# FBridge.net
KiCad netlist of a schematic drawn in Altium Designer
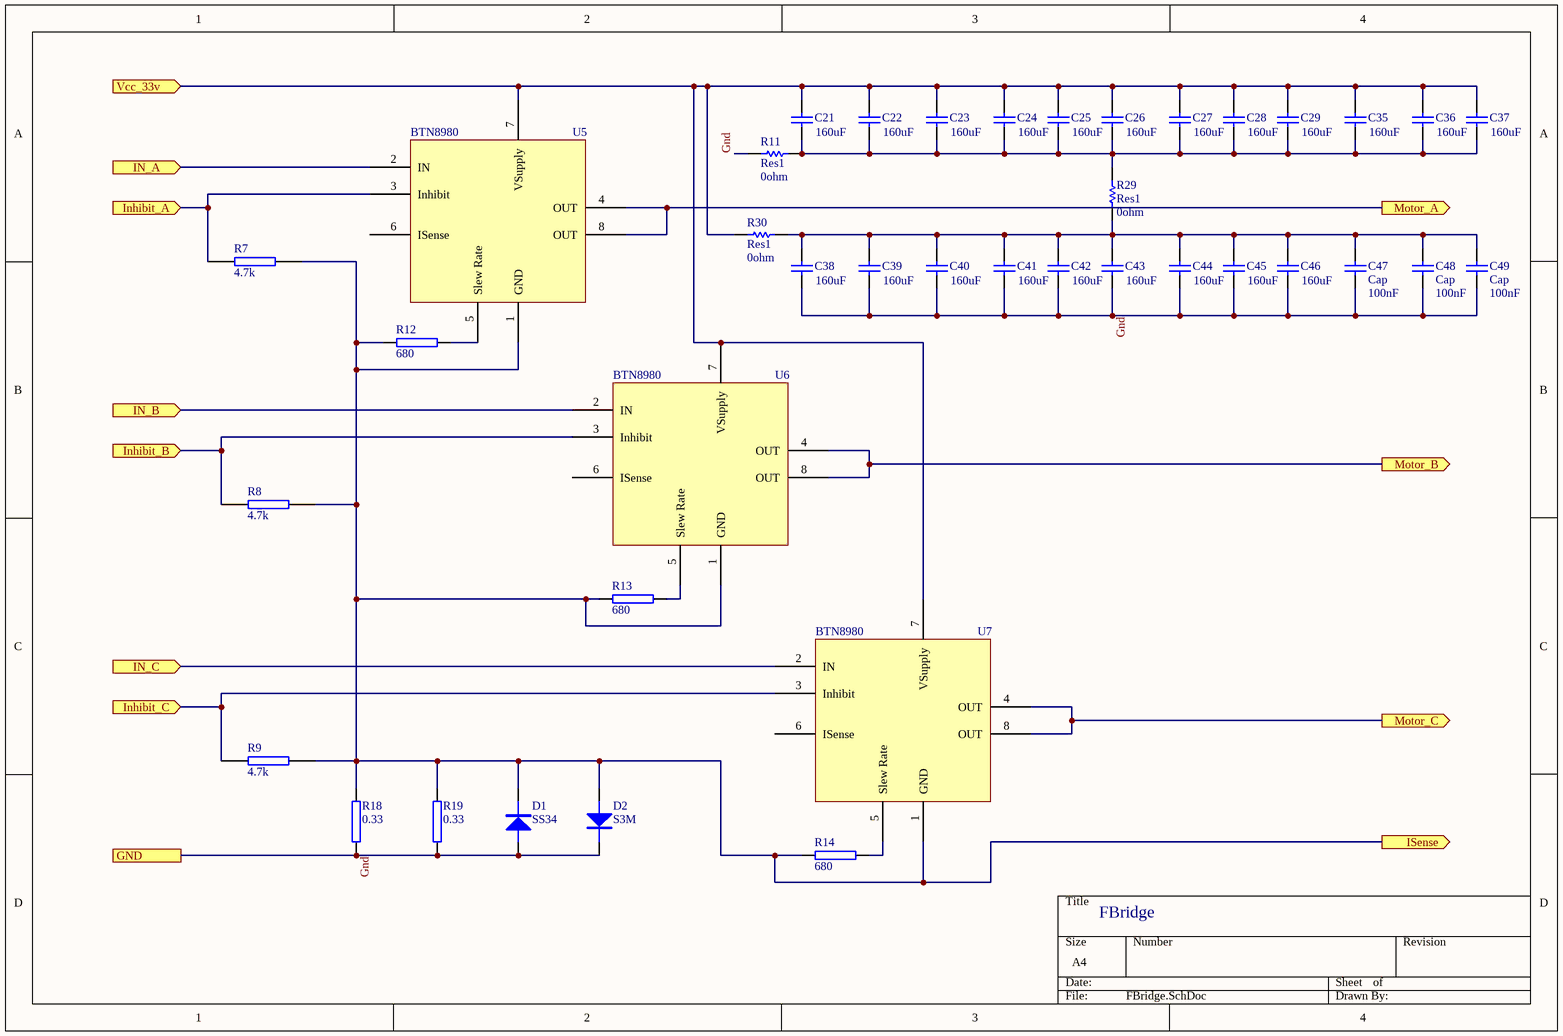
[diagram p0: FBridge.SchDoc]

(export (version "E")
  (design (tool "Eeschema 10.0.6"))
  (components
    (comp (ref "C21")
      (value "160uF")
      (footprint "Tantalum_9545")
      (description "Capacitor")
      (fields (field (name "Comment") "Cap") (field (name "PUBLISHER") "Altium Limited"))
      (libsource (lib "Miscellaneous Devices") (part "Cap"))
    )
    (comp (ref "C22")
      (value "160uF")
      (footprint "Tantalum_9545")
      (description "Capacitor")
      (fields (field (name "Comment") "Cap") (field (name "PUBLISHER") "Altium Limited"))
      (libsource (lib "Miscellaneous Devices") (part "Cap"))
    )
    (comp (ref "C23")
      (value "160uF")
      (footprint "Tantalum_9545")
      (description "Capacitor")
      (fields (field (name "Comment") "Cap") (field (name "PUBLISHER") "Altium Limited"))
      (libsource (lib "Miscellaneous Devices") (part "Cap"))
    )
    (comp (ref "C24")
      (value "160uF")
      (footprint "Tantalum_9545")
      (description "Capacitor")
      (fields (field (name "Comment") "Cap") (field (name "PUBLISHER") "Altium Limited"))
      (libsource (lib "Miscellaneous Devices") (part "Cap"))
    )
    (comp (ref "C25")
      (value "160uF")
      (footprint "Tantalum_9545")
      (description "Capacitor")
      (fields (field (name "Comment") "Cap") (field (name "PUBLISHER") "Altium Limited"))
      (libsource (lib "Miscellaneous Devices") (part "Cap"))
    )
    (comp (ref "C26")
      (value "160uF")
      (footprint "Tantalum_9545")
      (description "Capacitor")
      (fields (field (name "Comment") "Cap") (field (name "PUBLISHER") "Altium Limited"))
      (libsource (lib "Miscellaneous Devices") (part "Cap"))
    )
    (comp (ref "C27")
      (value "160uF")
      (footprint "Tantalum_9545")
      (description "Capacitor")
      (fields (field (name "Comment") "Cap") (field (name "PUBLISHER") "Altium Limited"))
      (libsource (lib "Miscellaneous Devices") (part "Cap"))
    )
    (comp (ref "C28")
      (value "160uF")
      (footprint "Tantalum_9545")
      (description "Capacitor")
      (fields (field (name "Comment") "Cap") (field (name "PUBLISHER") "Altium Limited"))
      (libsource (lib "Miscellaneous Devices") (part "Cap"))
    )
    (comp (ref "C29")
      (value "160uF")
      (footprint "Tantalum_9545")
      (description "Capacitor")
      (fields (field (name "Comment") "Cap") (field (name "PUBLISHER") "Altium Limited"))
      (libsource (lib "Miscellaneous Devices") (part "Cap"))
    )
    (comp (ref "C35")
      (value "160uF")
      (footprint "Tantalum_9545")
      (description "Capacitor")
      (fields (field (name "Comment") "Cap") (field (name "PUBLISHER") "Altium Limited"))
      (libsource (lib "Miscellaneous Devices") (part "Cap"))
    )
    (comp (ref "C36")
      (value "160uF")
      (footprint "Tantalum_9545")
      (description "Capacitor")
      (fields (field (name "Comment") "Cap") (field (name "PUBLISHER") "Altium Limited"))
      (libsource (lib "Miscellaneous Devices") (part "Cap"))
    )
    (comp (ref "C37")
      (value "160uF")
      (footprint "Tantalum_9545")
      (description "Capacitor")
      (fields (field (name "Comment") "Cap") (field (name "PUBLISHER") "Altium Limited"))
      (libsource (lib "Miscellaneous Devices") (part "Cap"))
    )
    (comp (ref "C38")
      (value "160uF")
      (footprint "Tantalum_9545")
      (description "Capacitor")
      (fields (field (name "Comment") "Cap") (field (name "PUBLISHER") "Altium Limited"))
      (libsource (lib "Miscellaneous Devices") (part "Cap"))
    )
    (comp (ref "C39")
      (value "160uF")
      (footprint "Tantalum_9545")
      (description "Capacitor")
      (fields (field (name "Comment") "Cap") (field (name "PUBLISHER") "Altium Limited"))
      (libsource (lib "Miscellaneous Devices") (part "Cap"))
    )
    (comp (ref "C40")
      (value "160uF")
      (footprint "Tantalum_9545")
      (description "Capacitor")
      (fields (field (name "Comment") "Cap") (field (name "PUBLISHER") "Altium Limited"))
      (libsource (lib "Miscellaneous Devices") (part "Cap"))
    )
    (comp (ref "C41")
      (value "160uF")
      (footprint "Tantalum_9545")
      (description "Capacitor")
      (fields (field (name "Comment") "Cap") (field (name "PUBLISHER") "Altium Limited"))
      (libsource (lib "Miscellaneous Devices") (part "Cap"))
    )
    (comp (ref "C42")
      (value "160uF")
      (footprint "Tantalum_9545")
      (description "Capacitor")
      (fields (field (name "Comment") "Cap") (field (name "PUBLISHER") "Altium Limited"))
      (libsource (lib "Miscellaneous Devices") (part "Cap"))
    )
    (comp (ref "C43")
      (value "160uF")
      (footprint "Tantalum_9545")
      (description "Capacitor")
      (fields (field (name "Comment") "Cap") (field (name "PUBLISHER") "Altium Limited"))
      (libsource (lib "Miscellaneous Devices") (part "Cap"))
    )
    (comp (ref "C44")
      (value "160uF")
      (footprint "Tantalum_9545")
      (description "Capacitor")
      (fields (field (name "Comment") "Cap") (field (name "PUBLISHER") "Altium Limited"))
      (libsource (lib "Miscellaneous Devices") (part "Cap"))
    )
    (comp (ref "C45")
      (value "160uF")
      (footprint "Tantalum_9545")
      (description "Capacitor")
      (fields (field (name "Comment") "Cap") (field (name "PUBLISHER") "Altium Limited"))
      (libsource (lib "Miscellaneous Devices") (part "Cap"))
    )
    (comp (ref "C46")
      (value "160uF")
      (footprint "Tantalum_9545")
      (description "Capacitor")
      (fields (field (name "Comment") "Cap") (field (name "PUBLISHER") "Altium Limited"))
      (libsource (lib "Miscellaneous Devices") (part "Cap"))
    )
    (comp (ref "C47")
      (value "Cap")
      (footprint "1206_SMD")
      (description "Capacitor")
      (fields (field (name "ALTIUM_VALUE") "100nF") (field (name "PUBLISHER") "Altium Limited"))
      (libsource (lib "Miscellaneous Devices") (part "Cap"))
    )
    (comp (ref "C48")
      (value "Cap")
      (footprint "1206_SMD")
      (description "Capacitor")
      (fields (field (name "ALTIUM_VALUE") "100nF") (field (name "PUBLISHER") "Altium Limited"))
      (libsource (lib "Miscellaneous Devices") (part "Cap"))
    )
    (comp (ref "C49")
      (value "Cap")
      (footprint "1206_SMD")
      (description "Capacitor")
      (fields (field (name "ALTIUM_VALUE") "100nF") (field (name "PUBLISHER") "Altium Limited"))
      (libsource (lib "Miscellaneous Devices") (part "Cap"))
    )
    (comp (ref "D1") (value "SS34") (footprint "SMA") (libsource (lib "Sch_Lib_24") (part "DIODE")))
    (comp (ref "D2") (value "S3M") (footprint "SMC") (libsource (lib "Sch_Lib_24") (part "DIODE")))
    (comp (ref "R7") (value "4.7k") (footprint "1206_SMD") (libsource (lib "") (part "RES2_1")))
    (comp (ref "R8") (value "4.7k") (footprint "1206_SMD") (libsource (lib "") (part "RES2_1")))
    (comp (ref "R9") (value "4.7k") (footprint "1206_SMD") (libsource (lib "") (part "RES2_1")))
    (comp (ref "R11")
      (value "Res1")
      (footprint "2010_smd")
      (description "Resistor")
      (fields (field (name "ALTIUM_VALUE") "0ohm") (field (name "PUBLISHER") "Altium Limited"))
      (libsource (lib "Miscellaneous Devices") (part "Res1"))
    )
    (comp (ref "R12") (value "680") (footprint "1206_SMD") (libsource (lib "Sch_Lib_24") (part "RES2")))
    (comp (ref "R13") (value "680") (footprint "1206_SMD") (libsource (lib "Sch_Lib_24") (part "RES2")))
    (comp (ref "R14") (value "680") (footprint "1206_SMD") (libsource (lib "Sch_Lib_24") (part "RES2")))
    (comp (ref "R18") (value "0.33") (footprint "2010_smd") (libsource (lib "Sch_Lib_24") (part "RES2")))
    (comp (ref "R19") (value "0.33") (footprint "2010_smd") (libsource (lib "Sch_Lib_24") (part "RES2")))
    (comp (ref "R29")
      (value "Res1")
      (footprint "2010_smd")
      (description "Resistor")
      (fields (field (name "ALTIUM_VALUE") "0ohm") (field (name "PUBLISHER") "Altium Limited"))
      (libsource (lib "Miscellaneous Devices") (part "Res1"))
    )
    (comp (ref "R30")
      (value "Res1")
      (footprint "2010_smd")
      (description "Resistor")
      (fields (field (name "ALTIUM_VALUE") "0ohm") (field (name "PUBLISHER") "Altium Limited"))
      (libsource (lib "Miscellaneous Devices") (part "Res1"))
    )
    (comp (ref "U5") (value "BTN8980") (footprint "TO263_7") (libsource (lib "Sch_Lib_24") (part "BTN8980")))
    (comp (ref "U6") (value "BTN8980") (footprint "TO263_7") (libsource (lib "Sch_Lib_24") (part "BTN8980")))
    (comp (ref "U7") (value "BTN8980") (footprint "TO263_7") (libsource (lib "Sch_Lib_24") (part "BTN8980")))
  )
  (nets
    (net (code "1") (name "/Gnd") (class "Default")
      (node (ref "C38") (pin "2") (pinfunction "2_2") (pintype "passive"))
      (node (ref "C39") (pin "2") (pinfunction "2_2") (pintype "passive"))
      (node (ref "C40") (pin "2") (pinfunction "2_2") (pintype "passive"))
      (node (ref "C41") (pin "2") (pinfunction "2_2") (pintype "passive"))
      (node (ref "C42") (pin "2") (pinfunction "2_2") (pintype "passive"))
      (node (ref "C43") (pin "2") (pinfunction "2_2") (pintype "passive"))
      (node (ref "C44") (pin "2") (pinfunction "2_2") (pintype "passive"))
      (node (ref "C45") (pin "2") (pinfunction "2_2") (pintype "passive"))
      (node (ref "C46") (pin "2") (pinfunction "2_2") (pintype "passive"))
      (node (ref "C47") (pin "1") (pinfunction "1_1") (pintype "passive"))
      (node (ref "C48") (pin "1") (pinfunction "1_1") (pintype "passive"))
      (node (ref "C49") (pin "1") (pinfunction "1_1") (pintype "passive"))
      (node (ref "D1") (pin "A") (pintype "passive"))
      (node (ref "D2") (pin "K") (pintype "passive"))
      (node (ref "R11") (pin "1") (pinfunction "1_1") (pintype "passive"))
      (node (ref "R18") (pin "1") (pintype "passive"))
      (node (ref "R19") (pin "1") (pintype "passive"))
    )
    (net (code "2") (name "/IN_A") (class "Default")
      (node (ref "U5") (pin "2") (pinfunction "IN_2") (pintype "passive"))
    )
    (net (code "3") (name "/IN_B") (class "Default")
      (node (ref "U6") (pin "2") (pinfunction "IN_2") (pintype "passive"))
    )
    (net (code "4") (name "/IN_C") (class "Default")
      (node (ref "U7") (pin "2") (pinfunction "IN_2") (pintype "passive"))
    )
    (net (code "5") (name "/ISense") (class "Default")
      (node (ref "D1") (pin "K") (pintype "passive"))
      (node (ref "D2") (pin "A") (pintype "passive"))
      (node (ref "R12") (pin "2") (pintype "passive"))
      (node (ref "R13") (pin "2") (pintype "passive"))
      (node (ref "R14") (pin "2") (pintype "passive"))
      (node (ref "R18") (pin "2") (pintype "passive"))
      (node (ref "R19") (pin "2") (pintype "passive"))
      (node (ref "R7") (pin "2") (pinfunction "2_2") (pintype "passive"))
      (node (ref "R8") (pin "2") (pinfunction "2_2") (pintype "passive"))
      (node (ref "R9") (pin "2") (pinfunction "2_2") (pintype "passive"))
      (node (ref "U5") (pin "1") (pinfunction "GND_1") (pintype "passive"))
      (node (ref "U6") (pin "1") (pinfunction "GND_1") (pintype "passive"))
      (node (ref "U7") (pin "1") (pinfunction "GND_1") (pintype "passive"))
    )
    (net (code "6") (name "/Inhibit_A") (class "Default")
      (node (ref "R7") (pin "1") (pinfunction "1_1") (pintype "passive"))
      (node (ref "U5") (pin "3") (pinfunction "Inhibit_3") (pintype "passive"))
    )
    (net (code "7") (name "/Inhibit_B") (class "Default")
      (node (ref "R8") (pin "1") (pinfunction "1_1") (pintype "passive"))
      (node (ref "U6") (pin "3") (pinfunction "Inhibit_3") (pintype "passive"))
    )
    (net (code "8") (name "/Inhibit_C") (class "Default")
      (node (ref "R9") (pin "1") (pinfunction "1_1") (pintype "passive"))
      (node (ref "U7") (pin "3") (pinfunction "Inhibit_3") (pintype "passive"))
    )
    (net (code "9") (name "/Motor_A") (class "Default")
      (node (ref "U5") (pin "4") (pinfunction "OUT_4") (pintype "passive"))
      (node (ref "U5") (pin "8") (pinfunction "OUT_8") (pintype "passive"))
    )
    (net (code "10") (name "/Motor_B") (class "Default")
      (node (ref "U6") (pin "4") (pinfunction "OUT_4") (pintype "passive"))
      (node (ref "U6") (pin "8") (pinfunction "OUT_8") (pintype "passive"))
    )
    (net (code "11") (name "/Motor_C") (class "Default")
      (node (ref "U7") (pin "4") (pinfunction "OUT_4") (pintype "passive"))
      (node (ref "U7") (pin "8") (pinfunction "OUT_8") (pintype "passive"))
    )
    (net (code "12") (name "/Vcc_33v") (class "Default")
      (node (ref "C21") (pin "1") (pinfunction "1_1") (pintype "passive"))
      (node (ref "C22") (pin "1") (pinfunction "1_1") (pintype "passive"))
      (node (ref "C23") (pin "1") (pinfunction "1_1") (pintype "passive"))
      (node (ref "C24") (pin "1") (pinfunction "1_1") (pintype "passive"))
      (node (ref "C25") (pin "1") (pinfunction "1_1") (pintype "passive"))
      (node (ref "C26") (pin "1") (pinfunction "1_1") (pintype "passive"))
      (node (ref "C27") (pin "1") (pinfunction "1_1") (pintype "passive"))
      (node (ref "C28") (pin "1") (pinfunction "1_1") (pintype "passive"))
      (node (ref "C29") (pin "1") (pinfunction "1_1") (pintype "passive"))
      (node (ref "C35") (pin "1") (pinfunction "1_1") (pintype "passive"))
      (node (ref "C36") (pin "1") (pinfunction "1_1") (pintype "passive"))
      (node (ref "C37") (pin "1") (pinfunction "1_1") (pintype "passive"))
      (node (ref "R30") (pin "1") (pinfunction "1_1") (pintype "passive"))
      (node (ref "U5") (pin "7") (pinfunction "VSupply_7") (pintype "passive"))
      (node (ref "U6") (pin "7") (pinfunction "VSupply_7") (pintype "passive"))
      (node (ref "U7") (pin "7") (pinfunction "VSupply_7") (pintype "passive"))
    )
    (net (code "13") (name "Net-(C21-Pad2)") (class "Default")
      (node (ref "C21") (pin "2") (pinfunction "2_2") (pintype "passive"))
      (node (ref "C22") (pin "2") (pinfunction "2_2") (pintype "passive"))
      (node (ref "C23") (pin "2") (pinfunction "2_2") (pintype "passive"))
      (node (ref "C24") (pin "2") (pinfunction "2_2") (pintype "passive"))
      (node (ref "C25") (pin "2") (pinfunction "2_2") (pintype "passive"))
      (node (ref "C26") (pin "2") (pinfunction "2_2") (pintype "passive"))
      (node (ref "C27") (pin "2") (pinfunction "2_2") (pintype "passive"))
      (node (ref "C28") (pin "2") (pinfunction "2_2") (pintype "passive"))
      (node (ref "C29") (pin "2") (pinfunction "2_2") (pintype "passive"))
      (node (ref "C35") (pin "2") (pinfunction "2_2") (pintype "passive"))
      (node (ref "C36") (pin "2") (pinfunction "2_2") (pintype "passive"))
      (node (ref "C37") (pin "2") (pinfunction "2_2") (pintype "passive"))
      (node (ref "R11") (pin "2") (pinfunction "2_2") (pintype "passive"))
      (node (ref "R29") (pin "2") (pinfunction "2_2") (pintype "passive"))
    )
    (net (code "14") (name "Net-(C38-Pad1)") (class "Default")
      (node (ref "C38") (pin "1") (pinfunction "1_1") (pintype "passive"))
      (node (ref "C39") (pin "1") (pinfunction "1_1") (pintype "passive"))
      (node (ref "C40") (pin "1") (pinfunction "1_1") (pintype "passive"))
      (node (ref "C41") (pin "1") (pinfunction "1_1") (pintype "passive"))
      (node (ref "C42") (pin "1") (pinfunction "1_1") (pintype "passive"))
      (node (ref "C43") (pin "1") (pinfunction "1_1") (pintype "passive"))
      (node (ref "C44") (pin "1") (pinfunction "1_1") (pintype "passive"))
      (node (ref "C45") (pin "1") (pinfunction "1_1") (pintype "passive"))
      (node (ref "C46") (pin "1") (pinfunction "1_1") (pintype "passive"))
      (node (ref "C47") (pin "2") (pinfunction "2_2") (pintype "passive"))
      (node (ref "C48") (pin "2") (pinfunction "2_2") (pintype "passive"))
      (node (ref "C49") (pin "2") (pinfunction "2_2") (pintype "passive"))
      (node (ref "R29") (pin "1") (pinfunction "1_1") (pintype "passive"))
      (node (ref "R30") (pin "2") (pinfunction "2_2") (pintype "passive"))
    )
    (net (code "15") (name "Net-(U5-Slew_Rate)") (class "Default")
      (node (ref "R12") (pin "1") (pintype "passive"))
      (node (ref "U5") (pin "5") (pinfunction "Slew_Rate_5") (pintype "passive"))
    )
    (net (code "16") (name "Net-(U6-Slew_Rate)") (class "Default")
      (node (ref "R13") (pin "1") (pintype "passive"))
      (node (ref "U6") (pin "5") (pinfunction "Slew_Rate_5") (pintype "passive"))
    )
    (net (code "17") (name "Net-(U7-Slew_Rate)") (class "Default")
      (node (ref "R14") (pin "1") (pintype "passive"))
      (node (ref "U7") (pin "5") (pinfunction "Slew_Rate_5") (pintype "passive"))
    )
    (net (code "18") (name "unconnected-(U5-ISense-Pad6)") (class "Default")
      (node (ref "U5") (pin "6") (pinfunction "ISense_6") (pintype "passive"))
    )
    (net (code "19") (name "unconnected-(U6-ISense-Pad6)") (class "Default")
      (node (ref "U6") (pin "6") (pinfunction "ISense_6") (pintype "passive"))
    )
    (net (code "20") (name "unconnected-(U7-ISense-Pad6)") (class "Default")
      (node (ref "U7") (pin "6") (pinfunction "ISense_6") (pintype "passive"))
    )
  )
)
